# switches.net
KiCad netlist of a schematic drawn in Altium Designer
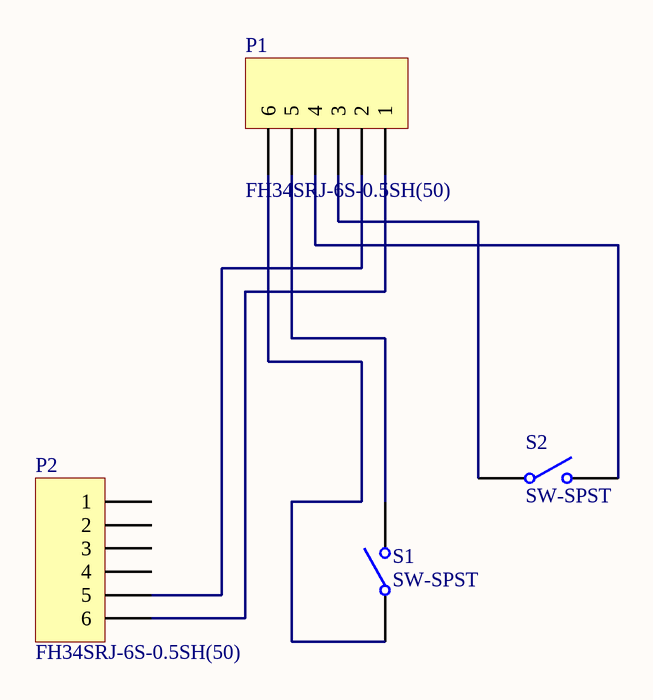
[diagram p0: switches.SchDoc]

(export (version "E")
  (design (tool "Eeschema 10.0.6"))
  (components
    (comp (ref "P1")
      (value "FH34SRJ-6S-0.5SH(50)")
      (footprint "HRS_FH34SRJ-6S-0.5SH(50)")
      (description "Header, 6-Pin")
      (fields (field (name "PUBLISHER") "Altium Limited"))
      (libsource (lib "Miscellaneous Connectors") (part "Header 6"))
    )
    (comp (ref "P2")
      (value "FH34SRJ-6S-0.5SH(50)")
      (footprint "HRS_FH34SRJ-6S-0.5SH(50)")
      (description "Header, 6-Pin")
      (fields (field (name "PUBLISHER") "Altium Limited"))
      (libsource (lib "") (part "Header 6_1"))
    )
    (comp (ref "S1")
      (value "SW-SPST")
      (footprint "ESE22MH22")
      (description "Single-Pole, Single-Throw Switch")
      (fields
        (field (name "MFG") "Panasonic")
        (field (name "MPN") "ESE22MH22")
        (field (name "PUBLISHER") "Altium Limited")
      )
      (libsource (lib "Miscellaneous Devices") (part "SW-SPST"))
    )
    (comp (ref "S2")
      (value "SW-SPST")
      (footprint "ESE22MH24")
      (description "Single-Pole, Single-Throw Switch")
      (fields
        (field (name "MFG") "Panasonic")
        (field (name "MPN") "ESE22MH24")
        (field (name "PUBLISHER") "Altium Limited")
      )
      (libsource (lib "Miscellaneous Devices") (part "SW-SPST"))
    )
  )
  (nets
    (net (code "1") (name "Net-(P1-Pad1)") (class "Default")
      (node (ref "P1") (pin "1") (pinfunction "1_1") (pintype "passive"))
      (node (ref "P2") (pin "6") (pinfunction "6_6") (pintype "passive"))
    )
    (net (code "2") (name "Net-(P1-Pad2)") (class "Default")
      (node (ref "P1") (pin "2") (pinfunction "2_2") (pintype "passive"))
      (node (ref "P2") (pin "5") (pinfunction "5_5") (pintype "passive"))
    )
    (net (code "3") (name "Net-(S1-COMMON)") (class "Default")
      (node (ref "P1") (pin "6") (pinfunction "6_6") (pintype "passive"))
      (node (ref "S1") (pin "1") (pinfunction "COMMON_1") (pintype "passive"))
    )
    (net (code "4") (name "Net-(S1-NO)") (class "Default")
      (node (ref "P1") (pin "5") (pinfunction "5_5") (pintype "passive"))
      (node (ref "S1") (pin "2") (pinfunction "NO_2") (pintype "passive"))
    )
    (net (code "5") (name "Net-(S2-COMMON)") (class "Default")
      (node (ref "P1") (pin "3") (pinfunction "3_3") (pintype "passive"))
      (node (ref "S2") (pin "1") (pinfunction "COMMON_1") (pintype "passive"))
    )
    (net (code "6") (name "Net-(S2-NO)") (class "Default")
      (node (ref "P1") (pin "4") (pinfunction "4_4") (pintype "passive"))
      (node (ref "S2") (pin "2") (pinfunction "NO_2") (pintype "passive"))
    )
    (net (code "7") (name "unconnected-(P2-Pad1)") (class "Default")
      (node (ref "P2") (pin "1") (pinfunction "1_1") (pintype "passive"))
    )
    (net (code "8") (name "unconnected-(P2-Pad2)") (class "Default")
      (node (ref "P2") (pin "2") (pinfunction "2_2") (pintype "passive"))
    )
    (net (code "9") (name "unconnected-(P2-Pad3)") (class "Default")
      (node (ref "P2") (pin "3") (pinfunction "3_3") (pintype "passive"))
    )
    (net (code "10") (name "unconnected-(P2-Pad4)") (class "Default")
      (node (ref "P2") (pin "4") (pinfunction "4_4") (pintype "passive"))
    )
  )
)
